# CBU_8266.net
KiCad netlist of a schematic drawn in Altium Designer
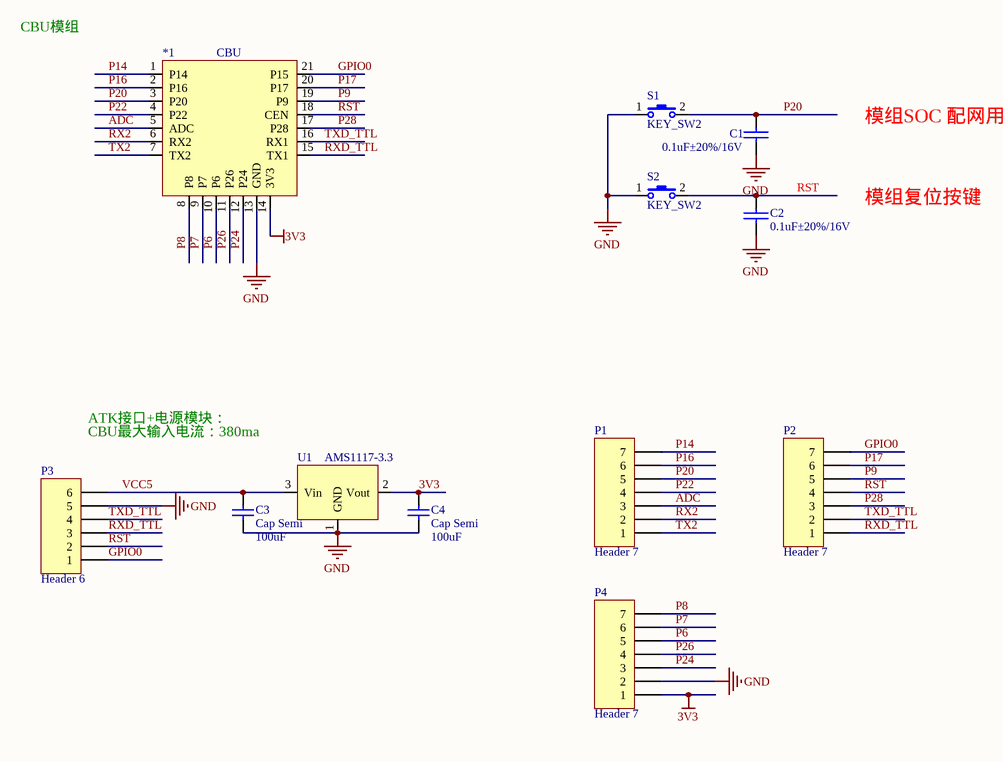
[diagram p0: CBU模块转8266封装.SchDoc]

(export (version "E")
  (design (tool "Eeschema 10.0.6"))
  (components
    (comp (ref "*1") (value "CBU") (libsource (lib "CBU模块转8266封装") (part "CBU")))
    (comp (ref "C1")
      (value "0.1uF±20%/16V")
      (footprint "C0603")
      (description "Capacitor")
      (libsource (lib "昊华元件库sch") (part "CAP"))
    )
    (comp (ref "C2")
      (value "0.1uF±20%/16V")
      (footprint "C0603")
      (description "Capacitor")
      (libsource (lib "昊华元件库sch") (part "CAP"))
    )
    (comp (ref "C3")
      (value "Cap Semi")
      (footprint "0402")
      (description "Capacitor (Semiconductor SIM Model)")
      (fields (field (name "ALTIUM_VALUE") "100uF") (field (name "PUBLISHER") "Altium Limited"))
      (libsource (lib "Miscellaneous Devices") (part "Cap Semi"))
    )
    (comp (ref "C4")
      (value "Cap Semi")
      (footprint "0402")
      (description "Capacitor (Semiconductor SIM Model)")
      (fields (field (name "ALTIUM_VALUE") "100uF") (field (name "PUBLISHER") "Altium Limited"))
      (libsource (lib "Miscellaneous Devices") (part "Cap Semi"))
    )
    (comp (ref "P1")
      (value "Header 7")
      (footprint "HDR1X7")
      (description "Header, 7-Pin")
      (fields (field (name "PUBLISHER") "Altium Limited"))
      (libsource (lib "Miscellaneous Connectors") (part "Header 7"))
    )
    (comp (ref "P2")
      (value "Header 7")
      (footprint "HDR1X7")
      (description "Header, 7-Pin")
      (fields (field (name "PUBLISHER") "Altium Limited"))
      (libsource (lib "Miscellaneous Connectors") (part "Header 7"))
    )
    (comp (ref "P3")
      (value "Header 6")
      (footprint "HDR1X6")
      (description "Header, 6-Pin")
      (fields (field (name "PUBLISHER") "Altium Limited"))
      (libsource (lib "Miscellaneous Connectors") (part "Header 6"))
    )
    (comp (ref "P4")
      (value "Header 7")
      (footprint "HDR1X7")
      (description "Header, 7-Pin")
      (fields (field (name "PUBLISHER") "Altium Limited"))
      (libsource (lib "Miscellaneous Connectors") (part "Header 7"))
    )
    (comp (ref "S1") (value "KEY_SW2") (footprint "KEY4-SMD") (libsource (lib "小马元件库sch") (part "KEY_SW2")))
    (comp (ref "S2") (value "KEY_SW2") (footprint "KEY4-SMD") (libsource (lib "小马元件库sch") (part "KEY_SW2")))
    (comp (ref "U1")
      (value "AMS1117-3.3")
      (footprint "SOT89")
      (libsource (lib "CBU模块转8266封装") (part "AMS1117"))
    )
  )
  (nets
    (net (code "1") (name "/ADC") (class "Default")
      (node (ref "*1") (pin "5") (pinfunction "ADC_5") (pintype "passive"))
      (node (ref "P1") (pin "3") (pinfunction "3_3") (pintype "passive"))
    )
    (net (code "2") (name "/GPIO0") (class "Default")
      (node (ref "*1") (pin "21") (pinfunction "P15_21") (pintype "passive"))
      (node (ref "P2") (pin "7") (pinfunction "7_7") (pintype "passive"))
      (node (ref "P3") (pin "1") (pinfunction "1_1") (pintype "passive"))
    )
    (net (code "3") (name "/P6") (class "Default")
      (node (ref "*1") (pin "10") (pinfunction "P6_10") (pintype "passive"))
      (node (ref "P4") (pin "5") (pinfunction "5_5") (pintype "passive"))
    )
    (net (code "4") (name "/P7") (class "Default")
      (node (ref "*1") (pin "9") (pinfunction "P7_9") (pintype "passive"))
      (node (ref "P4") (pin "6") (pinfunction "6_6") (pintype "passive"))
    )
    (net (code "5") (name "/P8") (class "Default")
      (node (ref "*1") (pin "8") (pinfunction "P8_8") (pintype "passive"))
      (node (ref "P4") (pin "7") (pinfunction "7_7") (pintype "passive"))
    )
    (net (code "6") (name "/P9") (class "Default")
      (node (ref "*1") (pin "19") (pinfunction "P9_19") (pintype "passive"))
      (node (ref "P2") (pin "5") (pinfunction "5_5") (pintype "passive"))
    )
    (net (code "7") (name "/P14") (class "Default")
      (node (ref "*1") (pin "1") (pinfunction "P14_1") (pintype "passive"))
      (node (ref "P1") (pin "7") (pinfunction "7_7") (pintype "passive"))
    )
    (net (code "8") (name "/P16") (class "Default")
      (node (ref "*1") (pin "2") (pinfunction "P16_2") (pintype "passive"))
      (node (ref "P1") (pin "6") (pinfunction "6_6") (pintype "passive"))
    )
    (net (code "9") (name "/P17") (class "Default")
      (node (ref "*1") (pin "20") (pinfunction "P17_20") (pintype "passive"))
      (node (ref "P2") (pin "6") (pinfunction "6_6") (pintype "passive"))
    )
    (net (code "10") (name "/P20") (class "Default")
      (node (ref "*1") (pin "3") (pinfunction "P20_3") (pintype "passive"))
      (node (ref "C1") (pin "2") (pinfunction "2_2") (pintype "passive"))
      (node (ref "P1") (pin "5") (pinfunction "5_5") (pintype "passive"))
      (node (ref "S1") (pin "2") (pinfunction "2_2") (pintype "passive"))
    )
    (net (code "11") (name "/P22") (class "Default")
      (node (ref "*1") (pin "4") (pinfunction "P22_4") (pintype "passive"))
      (node (ref "P1") (pin "4") (pinfunction "4_4") (pintype "passive"))
    )
    (net (code "12") (name "/P24") (class "Default")
      (node (ref "*1") (pin "12") (pinfunction "P24_12") (pintype "passive"))
      (node (ref "P4") (pin "3") (pinfunction "3_3") (pintype "passive"))
    )
    (net (code "13") (name "/P26") (class "Default")
      (node (ref "*1") (pin "11") (pinfunction "P26_11") (pintype "passive"))
      (node (ref "P4") (pin "4") (pinfunction "4_4") (pintype "passive"))
    )
    (net (code "14") (name "/P28") (class "Default")
      (node (ref "*1") (pin "17") (pinfunction "P28_17") (pintype "passive"))
      (node (ref "P2") (pin "3") (pinfunction "3_3") (pintype "passive"))
    )
    (net (code "15") (name "/RST") (class "Default")
      (node (ref "*1") (pin "18") (pinfunction "CEN_18") (pintype "passive"))
      (node (ref "C2") (pin "1") (pinfunction "1_1") (pintype "passive"))
      (node (ref "P2") (pin "4") (pinfunction "4_4") (pintype "passive"))
      (node (ref "P3") (pin "2") (pinfunction "2_2") (pintype "passive"))
      (node (ref "S2") (pin "2") (pinfunction "2_2") (pintype "passive"))
    )
    (net (code "16") (name "/RX2") (class "Default")
      (node (ref "*1") (pin "6") (pinfunction "RX2_6") (pintype "passive"))
      (node (ref "P1") (pin "2") (pinfunction "2_2") (pintype "passive"))
    )
    (net (code "17") (name "/RXD_TTL") (class "Default")
      (node (ref "*1") (pin "15") (pinfunction "TX1_15") (pintype "passive"))
      (node (ref "P2") (pin "1") (pinfunction "1_1") (pintype "passive"))
      (node (ref "P3") (pin "3") (pinfunction "3_3") (pintype "passive"))
    )
    (net (code "18") (name "/TX2") (class "Default")
      (node (ref "*1") (pin "7") (pinfunction "TX2_7") (pintype "passive"))
      (node (ref "P1") (pin "1") (pinfunction "1_1") (pintype "passive"))
    )
    (net (code "19") (name "/TXD_TTL") (class "Default")
      (node (ref "*1") (pin "16") (pinfunction "RX1_16") (pintype "passive"))
      (node (ref "P2") (pin "2") (pinfunction "2_2") (pintype "passive"))
      (node (ref "P3") (pin "4") (pinfunction "4_4") (pintype "passive"))
    )
    (net (code "20") (name "/VCC5") (class "Default")
      (node (ref "C3") (pin "2") (pinfunction "2_2") (pintype "passive"))
      (node (ref "P3") (pin "6") (pinfunction "6_6") (pintype "passive"))
      (node (ref "U1") (pin "3") (pinfunction "Vin_3") (pintype "passive"))
    )
    (net (code "21") (name "3V3") (class "Default")
      (node (ref "*1") (pin "14") (pinfunction "3V3_14") (pintype "passive"))
      (node (ref "C4") (pin "2") (pinfunction "2_2") (pintype "passive"))
      (node (ref "P4") (pin "1") (pinfunction "1_1") (pintype "passive"))
      (node (ref "U1") (pin "2") (pinfunction "Vout_2") (pintype "passive"))
    )
    (net (code "22") (name "GND") (class "Default")
      (node (ref "*1") (pin "13") (pinfunction "GND_13") (pintype "passive"))
      (node (ref "C1") (pin "1") (pinfunction "1_1") (pintype "passive"))
      (node (ref "C2") (pin "2") (pinfunction "2_2") (pintype "passive"))
      (node (ref "C3") (pin "1") (pinfunction "1_1") (pintype "passive"))
      (node (ref "C4") (pin "1") (pinfunction "1_1") (pintype "passive"))
      (node (ref "P3") (pin "5") (pinfunction "5_5") (pintype "passive"))
      (node (ref "P4") (pin "2") (pinfunction "2_2") (pintype "passive"))
      (node (ref "S1") (pin "1") (pinfunction "1_1") (pintype "passive"))
      (node (ref "S2") (pin "1") (pinfunction "1_1") (pintype "passive"))
      (node (ref "U1") (pin "1") (pinfunction "GND_1") (pintype "passive"))
    )
  )
)
